# TFT_LCD_ER-TFT018-2.net
KiCad netlist of a schematic drawn in Altium Designer
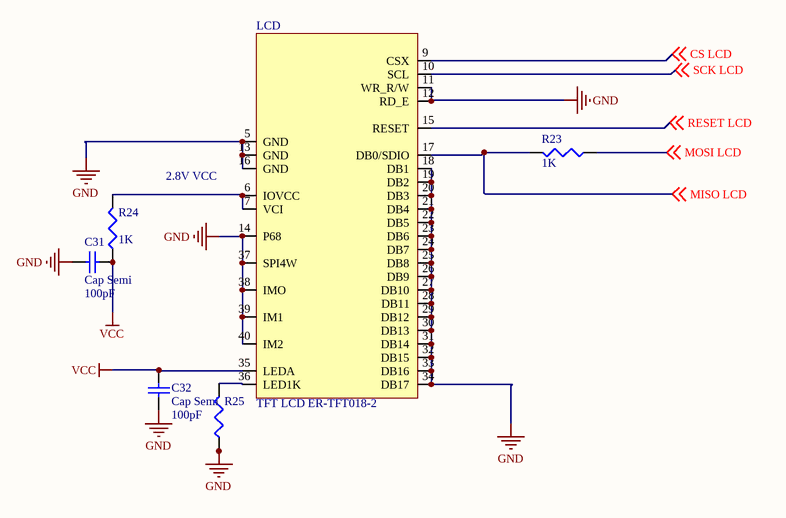
[diagram p0: TFT LCD ER-TFT018-2.SchDoc]

(export (version "E")
  (design (tool "Eeschema 10.0.6"))
  (components
    (comp (ref "C31")
      (value "Cap Semi")
      (footprint "C1206")
      (description "Capacitor (Semiconductor SIM Model)")
      (fields (field (name "ALTIUM_VALUE") "100pF") (field (name "PUBLISHER") "Altium Limited"))
      (libsource (lib "Miscellaneous Devices") (part "Cap Semi"))
    )
    (comp (ref "C32")
      (value "Cap Semi")
      (footprint "C1206")
      (description "Capacitor (Semiconductor SIM Model)")
      (fields (field (name "ALTIUM_VALUE") "100pF") (field (name "PUBLISHER") "Altium Limited"))
      (libsource (lib "Miscellaneous Devices") (part "Cap Semi"))
    )
    (comp (ref "LCD")
      (value "TFT LCD ER-TFT018-2")
      (footprint "LCD TFT Display")
      (libsource (lib "HGCDLibrary") (part "TFT LCD ER-TFT018-2"))
    )
    (comp (ref "R23")
      (value "1K")
      (footprint "J1-0603")
      (description "Resistor")
      (fields (field (name "Comment") "Res3") (field (name "PUBLISHER") "Altium Limited"))
      (libsource (lib "Miscellaneous Devices") (part "Res3"))
    )
    (comp (ref "R24")
      (value "1K")
      (footprint "J1-0603")
      (description "Resistor")
      (fields (field (name "Comment") "Res3") (field (name "PUBLISHER") "Altium Limited"))
      (libsource (lib "Miscellaneous Devices") (part "Res3"))
    )
    (comp (ref "R25")
      (value "Res3")
      (footprint "J1-0603")
      (description "Resistor")
      (fields (field (name "PUBLISHER") "Altium Limited"))
      (libsource (lib "Miscellaneous Devices") (part "Res3"))
    )
  )
  (nets
    (net (code "1") (name "CS LCD") (class "Default")
      (node (ref "LCD") (pin "9") (pinfunction "CSX_9") (pintype "bidirectional"))
    )
    (net (code "2") (name "GND") (class "Default")
      (node (ref "C31") (pin "1") (pinfunction "1_1") (pintype "passive"))
      (node (ref "C32") (pin "1") (pinfunction "1_1") (pintype "passive"))
      (node (ref "LCD") (pin "11") (pinfunction "WR_R/W_11") (pintype "bidirectional"))
      (node (ref "LCD") (pin "12") (pinfunction "RD_E_12") (pintype "bidirectional"))
      (node (ref "LCD") (pin "13") (pinfunction "GND_13") (pintype "power_in"))
      (node (ref "LCD") (pin "14") (pinfunction "P68_14") (pintype "power_in"))
      (node (ref "LCD") (pin "16") (pinfunction "GND_16") (pintype "power_in"))
      (node (ref "LCD") (pin "18") (pinfunction "DB1_18") (pintype "bidirectional"))
      (node (ref "LCD") (pin "19") (pinfunction "DB2_19") (pintype "bidirectional"))
      (node (ref "LCD") (pin "20") (pinfunction "DB3_20") (pintype "bidirectional"))
      (node (ref "LCD") (pin "21") (pinfunction "DB4_21") (pintype "bidirectional"))
      (node (ref "LCD") (pin "22") (pinfunction "DB5_22") (pintype "bidirectional"))
      (node (ref "LCD") (pin "23") (pinfunction "DB6_23") (pintype "bidirectional"))
      (node (ref "LCD") (pin "24") (pinfunction "DB7_24") (pintype "bidirectional"))
      (node (ref "LCD") (pin "25") (pinfunction "DB8_25") (pintype "bidirectional"))
      (node (ref "LCD") (pin "26") (pinfunction "DB9_26") (pintype "bidirectional"))
      (node (ref "LCD") (pin "27") (pinfunction "DB10_27") (pintype "bidirectional"))
      (node (ref "LCD") (pin "28") (pinfunction "DB11_28") (pintype "bidirectional"))
      (node (ref "LCD") (pin "29") (pinfunction "DB12_29") (pintype "bidirectional"))
      (node (ref "LCD") (pin "30") (pinfunction "DB13_30") (pintype "bidirectional"))
      (node (ref "LCD") (pin "31") (pinfunction "DB14_31") (pintype "bidirectional"))
      (node (ref "LCD") (pin "32") (pinfunction "DB15_32") (pintype "bidirectional"))
      (node (ref "LCD") (pin "33") (pinfunction "DB16_33") (pintype "bidirectional"))
      (node (ref "LCD") (pin "34") (pinfunction "DB17_34") (pintype "bidirectional"))
      (node (ref "LCD") (pin "37") (pinfunction "SPI4W_37") (pintype "power_in"))
      (node (ref "LCD") (pin "38") (pinfunction "IMO_38") (pintype "power_in"))
      (node (ref "LCD") (pin "39") (pinfunction "IM1_39") (pintype "power_in"))
      (node (ref "LCD") (pin "40") (pinfunction "IM2_40") (pintype "power_in"))
      (node (ref "LCD") (pin "5") (pinfunction "GND_5") (pintype "power_in"))
      (node (ref "R25") (pin "1") (pinfunction "1_1") (pintype "passive"))
    )
    (net (code "3") (name "MISO LCD") (class "Default")
      (node (ref "LCD") (pin "17") (pinfunction "DB0/SDIO_17") (pintype "bidirectional"))
      (node (ref "R23") (pin "2") (pinfunction "2_2") (pintype "passive"))
    )
    (net (code "4") (name "MOSI LCD") (class "Default")
      (node (ref "R23") (pin "1") (pinfunction "1_1") (pintype "passive"))
    )
    (net (code "5") (name "Net-(LCD-IOVCC)") (class "Default")
      (node (ref "LCD") (pin "6") (pinfunction "IOVCC_6") (pintype "power_in"))
      (node (ref "LCD") (pin "7") (pinfunction "VCI_7") (pintype "power_in"))
      (node (ref "R24") (pin "2") (pinfunction "2_2") (pintype "passive"))
    )
    (net (code "6") (name "Net-(LCD-LED1K)") (class "Default")
      (node (ref "LCD") (pin "36") (pinfunction "LED1K_36") (pintype "power_in"))
      (node (ref "R25") (pin "2") (pinfunction "2_2") (pintype "passive"))
    )
    (net (code "7") (name "RESET LCD") (class "Default")
      (node (ref "LCD") (pin "15") (pinfunction "RESET_15") (pintype "bidirectional"))
    )
    (net (code "8") (name "SCK LCD") (class "Default")
      (node (ref "LCD") (pin "10") (pinfunction "SCL_10") (pintype "bidirectional"))
    )
    (net (code "9") (name "VCC") (class "Default")
      (node (ref "C31") (pin "2") (pinfunction "2_2") (pintype "passive"))
      (node (ref "C32") (pin "2") (pinfunction "2_2") (pintype "passive"))
      (node (ref "LCD") (pin "35") (pinfunction "LEDA_35") (pintype "power_in"))
      (node (ref "R24") (pin "1") (pinfunction "1_1") (pintype "passive"))
    )
  )
)
